# Humidity_Regulator.net
KiCad netlist of a schematic drawn in Altium Designer
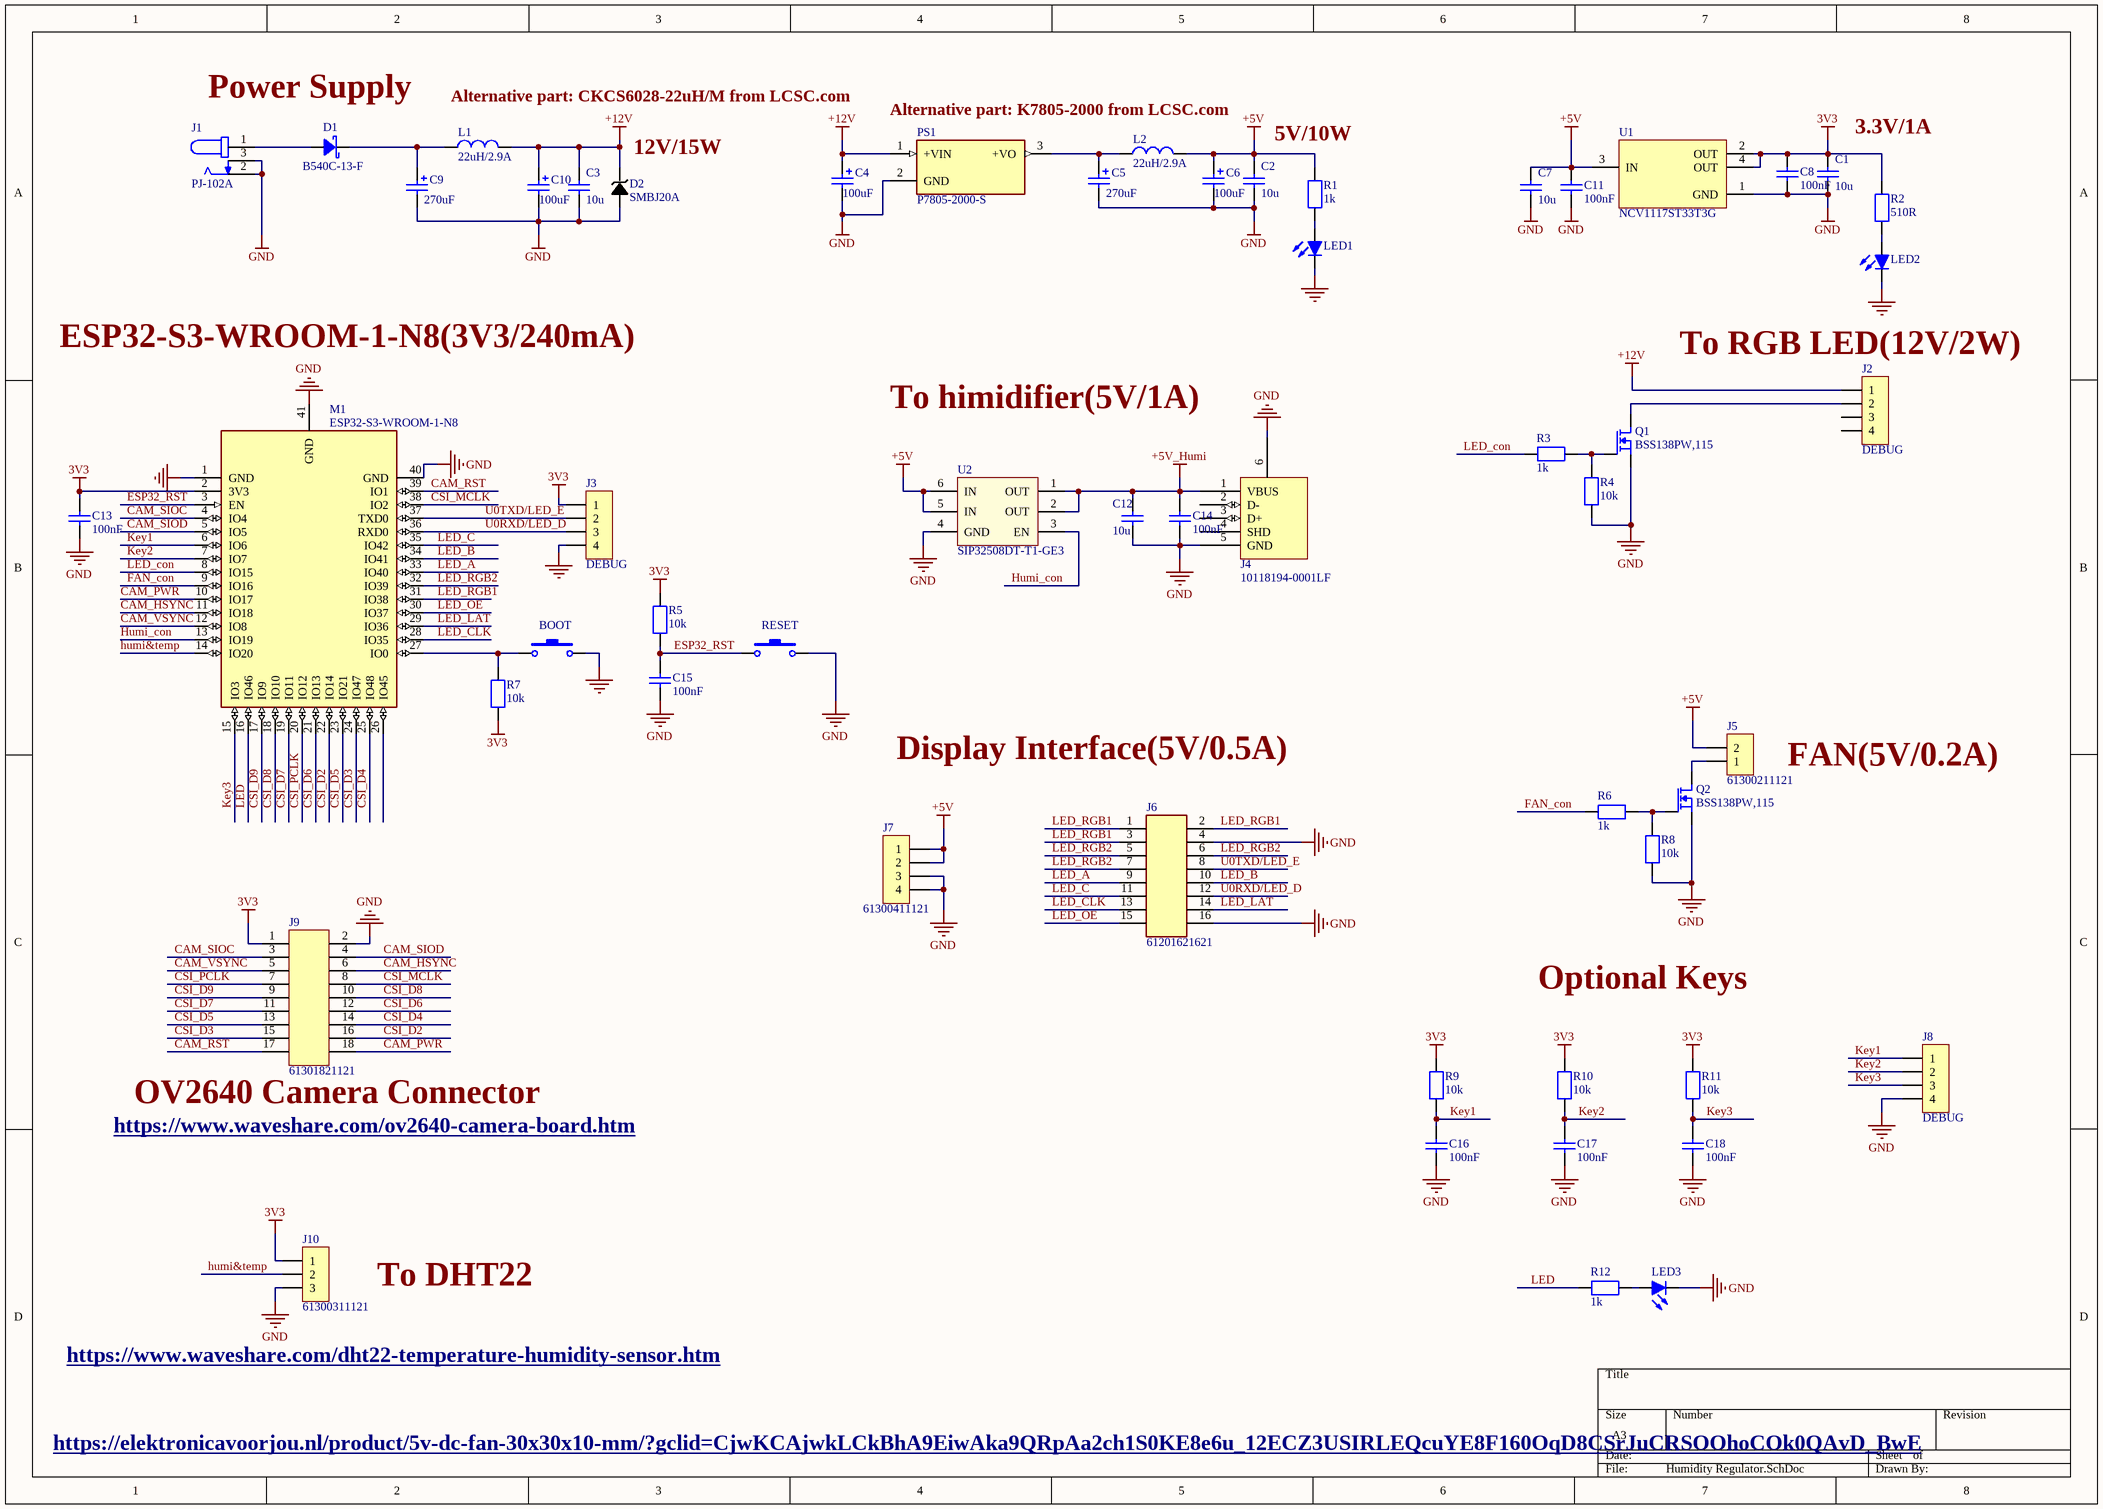
[diagram p0: Humidity Regulator.SchDoc]

(export (version "E")
  (design (tool "Eeschema 10.0.6"))
  (components
    (comp (ref "BOOT")
      (value "TL3305BF260QG")
      (footprint "SW_TL3305BF260QG")
      (description "SWITCH TACTILE SPST-NO 0.05A 12V")
      (fields (field (name "MANUFACTURER") "E-Switch"))
      (libsource (lib "Humidity Regulator") (part "TL3305BF260QG"))
    )
    (comp (ref "C1")
      (value "10u")
      (footprint "C1206")
      (description "10uF ± 10% 25V")
      (fields
        (field (name "MANUFACTURER") "Yageo")
        (field (name "MANUFACTURER PART NUMBER") "CC1206KKX7R8BB106")
      )
      (libsource (lib "Humidity Regulator") (part "10uF ± 10% 25V"))
    )
    (comp (ref "C2")
      (value "10u")
      (footprint "C1206")
      (description "10uF ± 10% 25V")
      (fields
        (field (name "MANUFACTURER") "Yageo")
        (field (name "MANUFACTURER PART NUMBER") "CC1206KKX7R8BB106")
      )
      (libsource (lib "Humidity Regulator") (part "10uF ± 10% 25V"))
    )
    (comp (ref "C3")
      (value "10u")
      (footprint "C1206")
      (description "10uF ± 10% 25V")
      (fields
        (field (name "MANUFACTURER") "Yageo")
        (field (name "MANUFACTURER PART NUMBER") "CC1206KKX7R8BB106")
      )
      (libsource (lib "Humidity Regulator") (part "10uF ± 10% 25V"))
    )
    (comp (ref "C4")
      (value "100uF")
      (footprint "CAP_EEUFC1E101S")
      (description "CAP ALUM 100UF 20% 25V SMD")
      (fields
        (field (name "MANUFACTURER PART NUMBER") "EEU-FC1E101S")
        (field (name "MANUFACTURER") "Panasonic")
      )
      (libsource (lib "Humidity Regulator") (part "EEU-FC1E101S"))
    )
    (comp (ref "C5")
      (value "270uF")
      (footprint "CAP_EEU-FK1E271B")
      (description "CAP ALUM 270UF 20% 25V SMD")
      (fields
        (field (name "MANUFACTURER PART NUMBER") "EEU-FC1E271B")
        (field (name "MANUFACTURER") "Panasonic")
      )
      (libsource (lib "Humidity Regulator") (part "EEU-FC1E271B"))
    )
    (comp (ref "C6")
      (value "100uF")
      (footprint "CAP_EEUFC1E101S")
      (description "CAP ALUM 100UF 20% 25V SMD")
      (fields
        (field (name "MANUFACTURER PART NUMBER") "EEU-FC1E101S")
        (field (name "MANUFACTURER") "Panasonic")
      )
      (libsource (lib "Humidity Regulator") (part "EEU-FC1E101S"))
    )
    (comp (ref "C7")
      (value "10u")
      (footprint "C1206")
      (description "10uF ± 10% 25V")
      (fields
        (field (name "MANUFACTURER") "Yageo")
        (field (name "MANUFACTURER PART NUMBER") "CC1206KKX7R8BB106")
      )
      (libsource (lib "Humidity Regulator") (part "10uF ± 10% 25V"))
    )
    (comp (ref "C8")
      (value "100nF")
      (footprint "C0603")
      (description "100nF ± 10% 50V")
      (fields
        (field (name "MANUFACTURER") "Yageo")
        (field (name "MANUFACTURER PART NUMBER") "CC0603KRX7R9BB104")
      )
      (libsource (lib "Humidity Regulator") (part "100nF ± 10% 50V"))
    )
    (comp (ref "C9")
      (value "270uF")
      (footprint "CAP_EEU-FK1E271B")
      (description "CAP ALUM 270UF 20% 25V SMD")
      (fields
        (field (name "MANUFACTURER PART NUMBER") "EEU-FC1E271B")
        (field (name "MANUFACTURER") "Panasonic")
      )
      (libsource (lib "Humidity Regulator") (part "EEU-FC1E271B"))
    )
    (comp (ref "C10")
      (value "100uF")
      (footprint "CAP_EEUFC1E101S")
      (description "CAP ALUM 100UF 20% 25V SMD")
      (fields
        (field (name "MANUFACTURER PART NUMBER") "EEU-FC1E101S")
        (field (name "MANUFACTURER") "Panasonic")
      )
      (libsource (lib "Humidity Regulator") (part "EEU-FC1E101S"))
    )
    (comp (ref "C11")
      (value "100nF")
      (footprint "C0603")
      (description "100nF ± 10% 50V")
      (fields
        (field (name "MANUFACTURER") "Yageo")
        (field (name "MANUFACTURER PART NUMBER") "CC0603KRX7R9BB104")
      )
      (libsource (lib "Humidity Regulator") (part "100nF ± 10% 50V"))
    )
    (comp (ref "C12")
      (value "10u")
      (footprint "C1206")
      (description "10uF ± 10% 25V")
      (fields
        (field (name "MANUFACTURER") "Yageo")
        (field (name "MANUFACTURER PART NUMBER") "CC1206KKX7R8BB106")
      )
      (libsource (lib "Humidity Regulator") (part "10uF ± 10% 25V"))
    )
    (comp (ref "C13")
      (value "100nF")
      (footprint "C0603")
      (description "100nF ± 10% 50V")
      (fields
        (field (name "MANUFACTURER") "Yageo")
        (field (name "MANUFACTURER PART NUMBER") "CC0603KRX7R9BB104")
      )
      (libsource (lib "Humidity Regulator") (part "100nF ± 10% 50V"))
    )
    (comp (ref "C14")
      (value "100nF")
      (footprint "C0603")
      (description "100nF ± 10% 50V")
      (fields
        (field (name "MANUFACTURER") "Yageo")
        (field (name "MANUFACTURER PART NUMBER") "CC0603KRX7R9BB104")
      )
      (libsource (lib "Humidity Regulator") (part "100nF ± 10% 50V"))
    )
    (comp (ref "C15")
      (value "100nF")
      (footprint "C0603")
      (description "100nF ± 10% 50V")
      (fields
        (field (name "MANUFACTURER") "Yageo")
        (field (name "MANUFACTURER PART NUMBER") "CC0603KRX7R9BB104")
      )
      (libsource (lib "Humidity Regulator") (part "100nF ± 10% 50V"))
    )
    (comp (ref "C16")
      (value "100nF")
      (footprint "C0603")
      (description "100nF ± 10% 50V")
      (fields
        (field (name "MANUFACTURER") "Yageo")
        (field (name "MANUFACTURER PART NUMBER") "CC0603KRX7R9BB104")
      )
      (libsource (lib "Humidity Regulator") (part "100nF ± 10% 50V"))
    )
    (comp (ref "C17")
      (value "100nF")
      (footprint "C0603")
      (description "100nF ± 10% 50V")
      (fields
        (field (name "MANUFACTURER") "Yageo")
        (field (name "MANUFACTURER PART NUMBER") "CC0603KRX7R9BB104")
      )
      (libsource (lib "Humidity Regulator") (part "100nF ± 10% 50V"))
    )
    (comp (ref "C18")
      (value "100nF")
      (footprint "C0603")
      (description "100nF ± 10% 50V")
      (fields
        (field (name "MANUFACTURER") "Yageo")
        (field (name "MANUFACTURER PART NUMBER") "CC0603KRX7R9BB104")
      )
      (libsource (lib "Humidity Regulator") (part "100nF ± 10% 50V"))
    )
    (comp (ref "D1")
      (value "B540C-13-F")
      (footprint "DO-214AB2")
      (description "Schottky Diodes & Rectifiers 40V 5A")
      (fields (field (name "MANUFACTURER") "Diodes"))
      (libsource (lib "Humidity Regulator") (part "B540C-13-F"))
    )
    (comp (ref "D2")
      (value "SMBJ20A")
      (footprint "DO-214AA2")
      (description "ESD Suppressors / TVS Diodes 600W, 23.4V, 5%, Unidirectional, TVS")
      (fields (field (name "MANUFACTURER") "Littelfuse"))
      (libsource (lib "Humidity Regulator") (part "ZM4746A-GS08"))
    )
    (comp (ref "J1")
      (value "PJ-102A")
      (footprint "CUI_PJ-102A")
      (description "CONN PWR JACK 2X5.5MM SOLDER")
      (fields (field (name "MANUFACTURER") "CUI Devices"))
      (libsource (lib "WirelessCharger") (part "PJ-102A"))
    )
    (comp (ref "J2")
      (value "DEBUG")
      (footprint "61300411121")
      (description "Headers & Wire Housings WR-PHD 2.54mm Hdr 4P Single Gold")
      (fields (field (name "MANUFACTURER") "Mouser") (field (name "MANUFACTURER PART NUMBER") "61300411121"))
      (libsource (lib "Humidity Regulator") (part "61300411121"))
    )
    (comp (ref "J3")
      (value "DEBUG")
      (footprint "61300411121")
      (description "Headers & Wire Housings WR-PHD 2.54mm Hdr 4P Single Gold")
      (fields (field (name "MANUFACTURER") "Mouser") (field (name "MANUFACTURER PART NUMBER") "61300411121"))
      (libsource (lib "Humidity Regulator") (part "61300411121"))
    )
    (comp (ref "J4")
      (value "10118194-0001LF")
      (footprint "10118194-0001LF")
      (description "CONN RCPT USB2.0 MICRO B SMD R/A")
      (fields (field (name "MANUFACTURER") "Amphenol FCI"))
      (libsource (lib "Humidity Regulator") (part "10118194-0001LF"))
    )
    (comp (ref "J5")
      (value "61300211121")
      (footprint "61300211121")
      (description "Headers & Wire Housings WR-PHD 2.54mm Hdr 2P Single Gold")
      (fields (field (name "MANUFACTURER") "Mouser"))
      (libsource (lib "Humidity Regulator") (part "61300211121"))
    )
    (comp (ref "J6")
      (value "61201621621")
      (footprint "61201621621:61201621621")
      (description "Connector Header Through Hole 16 position 0.100 (2.54mm)")
      (fields (field (name "MANUFACTURER") "Wurth Electronics"))
      (libsource (lib "Humidity Regulator") (part "61201621621"))
    )
    (comp (ref "J7")
      (value "61300411121")
      (footprint "61300411121")
      (description "Headers & Wire Housings WR-PHD 2.54mm Hdr 4P Single Gold")
      (fields (field (name "MANUFACTURER") "Mouser"))
      (libsource (lib "") (part "61300411121_1"))
    )
    (comp (ref "J8")
      (value "DEBUG")
      (footprint "61300411121")
      (description "Headers & Wire Housings WR-PHD 2.54mm Hdr 4P Single Gold")
      (fields (field (name "MANUFACTURER") "Mouser") (field (name "MANUFACTURER PART NUMBER") "61300411121"))
      (libsource (lib "Humidity Regulator") (part "61300411121"))
    )
    (comp (ref "J9")
      (value "61301821121")
      (footprint "61301821121")
      (description "Headers & Wire Housings WR-PHD 2.54mm Hdr 18 P Dual Str Gold")
      (fields (field (name "MANUFACTURER") "Wurth Electronics"))
      (libsource (lib "Humidity Regulator") (part "61301821121"))
    )
    (comp (ref "J10")
      (value "61300311121")
      (footprint "61300311121")
      (description "Headers & Wire Housings WR-PHD 2.54mm Hdr 3P Single Gold")
      (fields (field (name "MANUFACTURER") "Mouser"))
      (libsource (lib "Humidity Regulator") (part "61300311121"))
    )
    (comp (ref "L1")
      (value "22uH/2.9A")
      (footprint "IND_SRP6030")
      (description "Power Inductors - SMD Ind,7.1x6.6x2.8mm,22uH+/-20%,2.9A,shd")
      (fields
        (field (name "MANUFACTURER PART NUMBER") "SRP6030WA-220M")
        (field (name "MANUFACTURER") "Bourns")
      )
      (libsource (lib "Humidity Regulator") (part "SRP6030WA-220M"))
    )
    (comp (ref "L2")
      (value "22uH/2.9A")
      (footprint "IND_SRP6030")
      (description "Power Inductors - SMD Ind,7.1x6.6x2.8mm,22uH+/-20%,2.9A,shd")
      (fields
        (field (name "MANUFACTURER PART NUMBER") "SRP6030WA-220M")
        (field (name "MANUFACTURER") "Bourns")
      )
      (libsource (lib "Humidity Regulator") (part "SRP6030WA-220M"))
    )
    (comp (ref "LED1")
      (value "SML-D12U1WT86")
      (footprint "LED0603")
      (description "Typical RED GaAs LED")
      (fields (field (name "MANUFACTURER") "Rohm Semiconductor"))
      (libsource (lib "Humidity Regulator") (part "SML-D12U1WT86"))
    )
    (comp (ref "LED2")
      (value "SML-D12U1WT86")
      (footprint "LED0603")
      (description "Typical RED GaAs LED")
      (fields (field (name "MANUFACTURER") "Rohm Semiconductor"))
      (libsource (lib "Humidity Regulator") (part "SML-D12U1WT86"))
    )
    (comp (ref "LED3")
      (value "SML-D12U1WT86")
      (footprint "LED0603")
      (description "Typical RED GaAs LED")
      (fields (field (name "MANUFACTURER") "Rohm Semiconductor"))
      (libsource (lib "Humidity Regulator") (part "SML-D12U1WT86"))
    )
    (comp (ref "M1")
      (value "ESP32-S3-WROOM-1-N8")
      (footprint "ESP32-S3-WROOM-1-N8")
      (description "Bluetooth, WiFi 802.11b/g/n, Bluetooth v5.0 Transceiver Module 2.4GHz PCB Trace Surface Mount")
      (fields (field (name "MANUFACTURER") "Espressif Systems"))
      (libsource (lib "Humidity Regulator") (part "ESP32-S3-WROOM-1-N8"))
    )
    (comp (ref "PS1")
      (value "P7805-2000-S")
      (footprint "CONV_P7805-2000-S")
      (description "2 A Output Current, 6~36 Vdc Input, SIP, Non-Isolated, Dc-Dc Converter")
      (fields (field (name "MANUFACTURER") "CUI Inc."))
      (libsource (lib "P7805-2000-S") (part "P7805-2000-S"))
    )
    (comp (ref "Q1")
      (value "BSS138PW,115")
      (footprint "SOT323-3")
      (description "MOSFET, N CH, 60V, 0.2A")
      (fields (field (name "MANUFACTURER") "Nexperia"))
      (libsource (lib "Humidity Regulator") (part "BSS138PW,115"))
    )
    (comp (ref "Q2")
      (value "BSS138PW,115")
      (footprint "SOT323-3")
      (description "MOSFET, N CH, 60V, 0.2A")
      (fields (field (name "MANUFACTURER") "Nexperia"))
      (libsource (lib "Humidity Regulator") (part "BSS138PW,115"))
    )
    (comp (ref "R1")
      (value "1k")
      (footprint "R0603")
      (description "1 kOhms ±1% 0.1W")
      (fields
        (field (name "MANUFACTURER") "Yageo")
        (field (name "MANUFACTURER PART NUMBER") "RC0603FR-071KL")
      )
      (libsource (lib "Humidity Regulator") (part "1 kOhms ±1% 0.1W"))
    )
    (comp (ref "R2")
      (value "510R")
      (footprint "R0603")
      (description "510 Ohm ±1% 0.1W")
      (fields
        (field (name "MANUFACTURER") "Yageo")
        (field (name "MANUFACTURER PART NUMBER") "RC0603FR-07510RL")
      )
      (libsource (lib "Humidity Regulator") (part "510 Ohm ±1% 0.1W"))
    )
    (comp (ref "R3")
      (value "1k")
      (footprint "R0603")
      (description "1 kOhms ±1% 0.1W")
      (fields
        (field (name "MANUFACTURER") "Yageo")
        (field (name "MANUFACTURER PART NUMBER") "RC0603FR-071KL")
      )
      (libsource (lib "Humidity Regulator") (part "1 kOhms ±1% 0.1W"))
    )
    (comp (ref "R4")
      (value "10k")
      (footprint "R0603")
      (description "10 kOhms ±1% 0.1W")
      (fields
        (field (name "MANUFACTURER") "Yageo")
        (field (name "MANUFACTURER PART NUMBER") "RC0603FR-0710KL")
      )
      (libsource (lib "Humidity Regulator") (part "10 kOhms ±1% 0.1W"))
    )
    (comp (ref "R5")
      (value "10k")
      (footprint "R0603")
      (description "10 kOhms ±1% 0.1W")
      (fields
        (field (name "MANUFACTURER") "Yageo")
        (field (name "MANUFACTURER PART NUMBER") "RC0603FR-0710KL")
      )
      (libsource (lib "Humidity Regulator") (part "10 kOhms ±1% 0.1W"))
    )
    (comp (ref "R6")
      (value "1k")
      (footprint "R0603")
      (description "1 kOhms ±1% 0.1W")
      (fields
        (field (name "MANUFACTURER") "Yageo")
        (field (name "MANUFACTURER PART NUMBER") "RC0603FR-071KL")
      )
      (libsource (lib "Humidity Regulator") (part "1 kOhms ±1% 0.1W"))
    )
    (comp (ref "R7")
      (value "10k")
      (footprint "R0603")
      (description "10 kOhms ±1% 0.1W")
      (fields
        (field (name "MANUFACTURER") "Yageo")
        (field (name "MANUFACTURER PART NUMBER") "RC0603FR-0710KL")
      )
      (libsource (lib "Humidity Regulator") (part "10 kOhms ±1% 0.1W"))
    )
    (comp (ref "R8")
      (value "10k")
      (footprint "R0603")
      (description "10 kOhms ±1% 0.1W")
      (fields
        (field (name "MANUFACTURER") "Yageo")
        (field (name "MANUFACTURER PART NUMBER") "RC0603FR-0710KL")
      )
      (libsource (lib "Humidity Regulator") (part "10 kOhms ±1% 0.1W"))
    )
    (comp (ref "R9")
      (value "10k")
      (footprint "R0603")
      (description "10 kOhms ±1% 0.1W")
      (fields
        (field (name "MANUFACTURER") "Yageo")
        (field (name "MANUFACTURER PART NUMBER") "RC0603FR-0710KL")
      )
      (libsource (lib "Humidity Regulator") (part "10 kOhms ±1% 0.1W"))
    )
    (comp (ref "R10")
      (value "10k")
      (footprint "R0603")
      (description "10 kOhms ±1% 0.1W")
      (fields
        (field (name "MANUFACTURER") "Yageo")
        (field (name "MANUFACTURER PART NUMBER") "RC0603FR-0710KL")
      )
      (libsource (lib "Humidity Regulator") (part "10 kOhms ±1% 0.1W"))
    )
    (comp (ref "R11")
      (value "10k")
      (footprint "R0603")
      (description "10 kOhms ±1% 0.1W")
      (fields
        (field (name "MANUFACTURER") "Yageo")
        (field (name "MANUFACTURER PART NUMBER") "RC0603FR-0710KL")
      )
      (libsource (lib "Humidity Regulator") (part "10 kOhms ±1% 0.1W"))
    )
    (comp (ref "R12")
      (value "1k")
      (footprint "R0603")
      (description "1 kOhms ±1% 0.1W")
      (fields
        (field (name "MANUFACTURER") "Yageo")
        (field (name "MANUFACTURER PART NUMBER") "RC0603FR-071KL")
      )
      (libsource (lib "Humidity Regulator") (part "1 kOhms ±1% 0.1W"))
    )
    (comp (ref "RESET")
      (value "TL3305BF260QG")
      (footprint "SW_TL3305BF260QG")
      (description "SWITCH TACTILE SPST-NO 0.05A 12V")
      (fields (field (name "MANUFACTURER") "E-Switch"))
      (libsource (lib "Humidity Regulator") (part "TL3305BF260QG"))
    )
    (comp (ref "U1")
      (value "NCV1117ST33T3G")
      (footprint "SOT223-3")
      (description "LDO Voltage Regulators 3.3V 1.0A Automotive")
      (fields (field (name "MANUFACTURER") "onsemi"))
      (libsource (lib "Humidity Regulator") (part "NCV1117ST33T3G"))
    )
    (comp (ref "U2")
      (value "SIP32508DT-T1-GE3")
      (footprint "TSOT23-6")
      (description "Power Switch ICs - Power Distribution Slew Rate Controlled Load Switch")
      (fields (field (name "MANUFACTURER") "Vishay / Siliconix"))
      (libsource (lib "Humidity Regulator") (part "SIP32508DT-T1-GE3"))
    )
  )
  (nets
    (net (code "1") (name "+5V") (class "Default")
      (node (ref "C11") (pin "2") (pinfunction "2_2") (pintype "passive"))
      (node (ref "C2") (pin "2") (pinfunction "2_2") (pintype "passive"))
      (node (ref "C6") (pin "1") (pinfunction "1_1") (pintype "passive"))
      (node (ref "C7") (pin "2") (pinfunction "2_2") (pintype "passive"))
      (node (ref "J5") (pin "2") (pinfunction "2_2") (pintype "passive"))
      (node (ref "J7") (pin "1") (pinfunction "1_1") (pintype "passive"))
      (node (ref "J7") (pin "2") (pinfunction "2_2") (pintype "passive"))
      (node (ref "L2") (pin "2") (pinfunction "2_2") (pintype "passive"))
      (node (ref "R1") (pin "2") (pinfunction "2_2") (pintype "passive"))
      (node (ref "U1") (pin "3") (pinfunction "IN_3") (pintype "power_in"))
      (node (ref "U2") (pin "5") (pinfunction "IN_5") (pintype "passive"))
      (node (ref "U2") (pin "6") (pinfunction "IN_6") (pintype "passive"))
    )
    (net (code "2") (name "+5V_Humi") (class "Default")
      (node (ref "C12") (pin "2") (pinfunction "2_2") (pintype "passive"))
      (node (ref "C14") (pin "2") (pinfunction "2_2") (pintype "passive"))
      (node (ref "J4") (pin "1") (pinfunction "VBUS_1") (pintype "power_in"))
      (node (ref "U2") (pin "1") (pinfunction "OUT_1") (pintype "passive"))
      (node (ref "U2") (pin "2") (pinfunction "OUT_2") (pintype "passive"))
    )
    (net (code "3") (name "+12V") (class "Default")
      (node (ref "C10") (pin "1") (pinfunction "1_1") (pintype "passive"))
      (node (ref "C3") (pin "2") (pinfunction "2_2") (pintype "passive"))
      (node (ref "C4") (pin "1") (pinfunction "1_1") (pintype "passive"))
      (node (ref "D2") (pin "C") (pinfunction "C_C") (pintype "passive"))
      (node (ref "J2") (pin "1") (pinfunction "1_1") (pintype "passive"))
      (node (ref "L1") (pin "2") (pinfunction "2_2") (pintype "passive"))
      (node (ref "PS1") (pin "1") (pinfunction "+VIN_1") (pintype "input"))
    )
    (net (code "4") (name "/CAM_HSYNC") (class "Default")
      (node (ref "J9") (pin "6") (pinfunction "6_6") (pintype "passive"))
      (node (ref "M1") (pin "11") (pinfunction "IO18_11") (pintype "bidirectional"))
    )
    (net (code "5") (name "/CAM_PWR") (class "Default")
      (node (ref "J9") (pin "18") (pinfunction "18_18") (pintype "passive"))
      (node (ref "M1") (pin "10") (pinfunction "IO17_10") (pintype "bidirectional"))
    )
    (net (code "6") (name "/CAM_RST") (class "Default")
      (node (ref "J9") (pin "17") (pinfunction "17_17") (pintype "passive"))
      (node (ref "M1") (pin "39") (pinfunction "IO1_39") (pintype "bidirectional"))
    )
    (net (code "7") (name "/CAM_SIOC") (class "Default")
      (node (ref "J9") (pin "3") (pinfunction "3_3") (pintype "passive"))
      (node (ref "M1") (pin "4") (pinfunction "IO4_4") (pintype "bidirectional"))
    )
    (net (code "8") (name "/CAM_SIOD") (class "Default")
      (node (ref "J9") (pin "4") (pinfunction "4_4") (pintype "passive"))
      (node (ref "M1") (pin "5") (pinfunction "IO5_5") (pintype "bidirectional"))
    )
    (net (code "9") (name "/CAM_VSYNC") (class "Default")
      (node (ref "J9") (pin "5") (pinfunction "5_5") (pintype "passive"))
      (node (ref "M1") (pin "12") (pinfunction "IO8_12") (pintype "bidirectional"))
    )
    (net (code "10") (name "/CSI_D2") (class "Default")
      (node (ref "J9") (pin "16") (pinfunction "16_16") (pintype "passive"))
      (node (ref "M1") (pin "22") (pinfunction "IO14_22") (pintype "bidirectional"))
    )
    (net (code "11") (name "/CSI_D3") (class "Default")
      (node (ref "J9") (pin "15") (pinfunction "15_15") (pintype "passive"))
      (node (ref "M1") (pin "24") (pinfunction "IO47_24") (pintype "bidirectional"))
    )
    (net (code "12") (name "/CSI_D4") (class "Default")
      (node (ref "J9") (pin "14") (pinfunction "14_14") (pintype "passive"))
      (node (ref "M1") (pin "25") (pinfunction "IO48_25") (pintype "bidirectional"))
    )
    (net (code "13") (name "/CSI_D5") (class "Default")
      (node (ref "J9") (pin "13") (pinfunction "13_13") (pintype "passive"))
      (node (ref "M1") (pin "23") (pinfunction "IO21_23") (pintype "bidirectional"))
    )
    (net (code "14") (name "/CSI_D6") (class "Default")
      (node (ref "J9") (pin "12") (pinfunction "12_12") (pintype "passive"))
      (node (ref "M1") (pin "21") (pinfunction "IO13_21") (pintype "bidirectional"))
    )
    (net (code "15") (name "/CSI_D7") (class "Default")
      (node (ref "J9") (pin "11") (pinfunction "11_11") (pintype "passive"))
      (node (ref "M1") (pin "19") (pinfunction "IO11_19") (pintype "bidirectional"))
    )
    (net (code "16") (name "/CSI_D8") (class "Default")
      (node (ref "J9") (pin "10") (pinfunction "10_10") (pintype "passive"))
      (node (ref "M1") (pin "18") (pinfunction "IO10_18") (pintype "bidirectional"))
    )
    (net (code "17") (name "/CSI_D9") (class "Default")
      (node (ref "J9") (pin "9") (pinfunction "9_9") (pintype "passive"))
      (node (ref "M1") (pin "17") (pinfunction "IO9_17") (pintype "bidirectional"))
    )
    (net (code "18") (name "/CSI_MCLK") (class "Default")
      (node (ref "J9") (pin "8") (pinfunction "8_8") (pintype "passive"))
      (node (ref "M1") (pin "38") (pinfunction "IO2_38") (pintype "bidirectional"))
    )
    (net (code "19") (name "/CSI_PCLK") (class "Default")
      (node (ref "J9") (pin "7") (pinfunction "7_7") (pintype "passive"))
      (node (ref "M1") (pin "20") (pinfunction "IO12_20") (pintype "bidirectional"))
    )
    (net (code "20") (name "/ESP32_RST") (class "Default")
      (node (ref "C15") (pin "2") (pinfunction "2_2") (pintype "passive"))
      (node (ref "M1") (pin "3") (pinfunction "EN_3") (pintype "input"))
      (node (ref "R5") (pin "1") (pinfunction "1_1") (pintype "passive"))
      (node (ref "RESET") (pin "1") (pinfunction "1_1") (pintype "passive"))
    )
    (net (code "21") (name "/FAN_con") (class "Default")
      (node (ref "M1") (pin "9") (pinfunction "IO16_9") (pintype "bidirectional"))
      (node (ref "R6") (pin "1") (pinfunction "1_1") (pintype "passive"))
    )
    (net (code "22") (name "/Humi_con") (class "Default")
      (node (ref "M1") (pin "13") (pinfunction "IO19_13") (pintype "bidirectional"))
      (node (ref "U2") (pin "3") (pinfunction "EN_3") (pintype "passive"))
    )
    (net (code "23") (name "/Key1") (class "Default")
      (node (ref "C16") (pin "2") (pinfunction "2_2") (pintype "passive"))
      (node (ref "J8") (pin "1") (pinfunction "1_1") (pintype "passive"))
      (node (ref "M1") (pin "6") (pinfunction "IO6_6") (pintype "bidirectional"))
      (node (ref "R9") (pin "1") (pinfunction "1_1") (pintype "passive"))
    )
    (net (code "24") (name "/Key2") (class "Default")
      (node (ref "C17") (pin "2") (pinfunction "2_2") (pintype "passive"))
      (node (ref "J8") (pin "2") (pinfunction "2_2") (pintype "passive"))
      (node (ref "M1") (pin "7") (pinfunction "IO7_7") (pintype "bidirectional"))
      (node (ref "R10") (pin "1") (pinfunction "1_1") (pintype "passive"))
    )
    (net (code "25") (name "/Key3") (class "Default")
      (node (ref "C18") (pin "2") (pinfunction "2_2") (pintype "passive"))
      (node (ref "J8") (pin "3") (pinfunction "3_3") (pintype "passive"))
      (node (ref "M1") (pin "15") (pinfunction "IO3_15") (pintype "bidirectional"))
      (node (ref "R11") (pin "1") (pinfunction "1_1") (pintype "passive"))
    )
    (net (code "26") (name "/LED") (class "Default")
      (node (ref "M1") (pin "16") (pinfunction "IO46_16") (pintype "bidirectional"))
      (node (ref "R12") (pin "2") (pinfunction "2_2") (pintype "passive"))
    )
    (net (code "27") (name "/LED_A") (class "Default")
      (node (ref "J6") (pin "9") (pinfunction "9_9") (pintype "passive"))
      (node (ref "M1") (pin "33") (pinfunction "IO40_33") (pintype "bidirectional"))
    )
    (net (code "28") (name "/LED_B") (class "Default")
      (node (ref "J6") (pin "10") (pinfunction "10_10") (pintype "passive"))
      (node (ref "M1") (pin "34") (pinfunction "IO41_34") (pintype "bidirectional"))
    )
    (net (code "29") (name "/LED_C") (class "Default")
      (node (ref "J6") (pin "11") (pinfunction "11_11") (pintype "passive"))
      (node (ref "M1") (pin "35") (pinfunction "IO42_35") (pintype "bidirectional"))
    )
    (net (code "30") (name "/LED_CLK") (class "Default")
      (node (ref "J6") (pin "13") (pinfunction "13_13") (pintype "passive"))
      (node (ref "M1") (pin "28") (pinfunction "IO35_28") (pintype "bidirectional"))
    )
    (net (code "31") (name "/LED_LAT") (class "Default")
      (node (ref "J6") (pin "14") (pinfunction "14_14") (pintype "passive"))
      (node (ref "M1") (pin "29") (pinfunction "IO36_29") (pintype "bidirectional"))
    )
    (net (code "32") (name "/LED_OE") (class "Default")
      (node (ref "J6") (pin "15") (pinfunction "15_15") (pintype "passive"))
      (node (ref "M1") (pin "30") (pinfunction "IO37_30") (pintype "bidirectional"))
    )
    (net (code "33") (name "/LED_RGB1") (class "Default")
      (node (ref "J6") (pin "1") (pinfunction "1_1") (pintype "passive"))
      (node (ref "J6") (pin "2") (pinfunction "2_2") (pintype "passive"))
      (node (ref "J6") (pin "3") (pinfunction "3_3") (pintype "passive"))
      (node (ref "M1") (pin "31") (pinfunction "IO38_31") (pintype "bidirectional"))
    )
    (net (code "34") (name "/LED_RGB2") (class "Default")
      (node (ref "J6") (pin "5") (pinfunction "5_5") (pintype "passive"))
      (node (ref "J6") (pin "6") (pinfunction "6_6") (pintype "passive"))
      (node (ref "J6") (pin "7") (pinfunction "7_7") (pintype "passive"))
      (node (ref "M1") (pin "32") (pinfunction "IO39_32") (pintype "bidirectional"))
    )
    (net (code "35") (name "/LED_con") (class "Default")
      (node (ref "M1") (pin "8") (pinfunction "IO15_8") (pintype "bidirectional"))
      (node (ref "R3") (pin "1") (pinfunction "1_1") (pintype "passive"))
    )
    (net (code "36") (name "/U0RXD{slash}LED_D") (class "Default")
      (node (ref "J3") (pin "3") (pinfunction "3_3") (pintype "passive"))
      (node (ref "J6") (pin "12") (pinfunction "12_12") (pintype "passive"))
      (node (ref "M1") (pin "36") (pinfunction "RXD0_36") (pintype "bidirectional"))
    )
    (net (code "37") (name "/U0TXD{slash}LED_E") (class "Default")
      (node (ref "J3") (pin "2") (pinfunction "2_2") (pintype "passive"))
      (node (ref "J6") (pin "8") (pinfunction "8_8") (pintype "passive"))
      (node (ref "M1") (pin "37") (pinfunction "TXD0_37") (pintype "bidirectional"))
    )
    (net (code "38") (name "/humi&temp") (class "Default")
      (node (ref "J10") (pin "2") (pinfunction "2_2") (pintype "passive"))
      (node (ref "M1") (pin "14") (pinfunction "IO20_14") (pintype "bidirectional"))
    )
    (net (code "39") (name "3V3") (class "Default")
      (node (ref "C1") (pin "2") (pinfunction "2_2") (pintype "passive"))
      (node (ref "C13") (pin "2") (pinfunction "2_2") (pintype "passive"))
      (node (ref "C8") (pin "2") (pinfunction "2_2") (pintype "passive"))
      (node (ref "J10") (pin "1") (pinfunction "1_1") (pintype "passive"))
      (node (ref "J3") (pin "1") (pinfunction "1_1") (pintype "passive"))
      (node (ref "J9") (pin "1") (pinfunction "1_1") (pintype "passive"))
      (node (ref "M1") (pin "2") (pinfunction "3V3_2") (pintype "power_in"))
      (node (ref "R10") (pin "2") (pinfunction "2_2") (pintype "passive"))
      (node (ref "R11") (pin "2") (pinfunction "2_2") (pintype "passive"))
      (node (ref "R2") (pin "2") (pinfunction "2_2") (pintype "passive"))
      (node (ref "R5") (pin "2") (pinfunction "2_2") (pintype "passive"))
      (node (ref "R7") (pin "2") (pinfunction "2_2") (pintype "passive"))
      (node (ref "R9") (pin "2") (pinfunction "2_2") (pintype "passive"))
      (node (ref "U1") (pin "2") (pinfunction "OUT_2") (pintype "power_in"))
      (node (ref "U1") (pin "4") (pinfunction "OUT_4") (pintype "power_in"))
    )
    (net (code "40") (name "GND") (class "Default")
      (node (ref "BOOT") (pin "2") (pinfunction "2_2") (pintype "passive"))
      (node (ref "C1") (pin "1") (pinfunction "1_1") (pintype "passive"))
      (node (ref "C10") (pin "2") (pinfunction "2_2") (pintype "passive"))
      (node (ref "C11") (pin "1") (pinfunction "1_1") (pintype "passive"))
      (node (ref "C12") (pin "1") (pinfunction "1_1") (pintype "passive"))
      (node (ref "C13") (pin "1") (pinfunction "1_1") (pintype "passive"))
      (node (ref "C14") (pin "1") (pinfunction "1_1") (pintype "passive"))
      (node (ref "C15") (pin "1") (pinfunction "1_1") (pintype "passive"))
      (node (ref "C16") (pin "1") (pinfunction "1_1") (pintype "passive"))
      (node (ref "C17") (pin "1") (pinfunction "1_1") (pintype "passive"))
      (node (ref "C18") (pin "1") (pinfunction "1_1") (pintype "passive"))
      (node (ref "C2") (pin "1") (pinfunction "1_1") (pintype "passive"))
      (node (ref "C3") (pin "1") (pinfunction "1_1") (pintype "passive"))
      (node (ref "C4") (pin "2") (pinfunction "2_2") (pintype "passive"))
      (node (ref "C5") (pin "2") (pinfunction "2_2") (pintype "passive"))
      (node (ref "C6") (pin "2") (pinfunction "2_2") (pintype "passive"))
      (node (ref "C7") (pin "1") (pinfunction "1_1") (pintype "passive"))
      (node (ref "C8") (pin "1") (pinfunction "1_1") (pintype "passive"))
      (node (ref "C9") (pin "2") (pinfunction "2_2") (pintype "passive"))
      (node (ref "D2") (pin "A") (pinfunction "A_A") (pintype "passive"))
      (node (ref "J1") (pin "2") (pinfunction "2_2") (pintype "passive"))
      (node (ref "J1") (pin "3") (pinfunction "3_3") (pintype "passive"))
      (node (ref "J10") (pin "3") (pinfunction "3_3") (pintype "passive"))
      (node (ref "J3") (pin "4") (pinfunction "4_4") (pintype "passive"))
      (node (ref "J4") (pin "5") (pinfunction "GND_5") (pintype "power_in"))
      (node (ref "J4") (pin "6") (pintype "passive"))
      (node (ref "J6") (pin "16") (pinfunction "16_16") (pintype "passive"))
      (node (ref "J6") (pin "4") (pinfunction "4_4") (pintype "passive"))
      (node (ref "J7") (pin "3") (pinfunction "3_3") (pintype "passive"))
      (node (ref "J7") (pin "4") (pinfunction "4_4") (pintype "passive"))
      (node (ref "J8") (pin "4") (pinfunction "4_4") (pintype "passive"))
      (node (ref "J9") (pin "2") (pinfunction "2_2") (pintype "passive"))
      (node (ref "LED1") (pin "C") (pinfunction "C_C") (pintype "passive"))
      (node (ref "LED2") (pin "C") (pinfunction "C_C") (pintype "passive"))
      (node (ref "LED3") (pin "C") (pinfunction "C_C") (pintype "passive"))
      (node (ref "M1") (pin "1") (pinfunction "GND_1") (pintype "power_in"))
      (node (ref "M1") (pin "40") (pinfunction "GND_40") (pintype "power_in"))
      (node (ref "M1") (pin "41") (pinfunction "GND_41") (pintype "power_in"))
      (node (ref "PS1") (pin "2") (pinfunction "GND_2") (pintype "power_in"))
      (node (ref "Q1") (pin "2") (pinfunction "S_2") (pintype "passive"))
      (node (ref "Q2") (pin "2") (pinfunction "S_2") (pintype "passive"))
      (node (ref "R4") (pin "1") (pinfunction "1_1") (pintype "passive"))
      (node (ref "R8") (pin "1") (pinfunction "1_1") (pintype "passive"))
      (node (ref "RESET") (pin "2") (pinfunction "2_2") (pintype "passive"))
      (node (ref "U1") (pin "1") (pinfunction "GND_1") (pintype "power_in"))
      (node (ref "U2") (pin "4") (pinfunction "GND_4") (pintype "passive"))
    )
    (net (code "41") (name "Net-(C9-Pad1)") (class "Default")
      (node (ref "C9") (pin "1") (pinfunction "1_1") (pintype "passive"))
      (node (ref "D1") (pin "C") (pinfunction "C_C") (pintype "passive"))
      (node (ref "L1") (pin "1") (pinfunction "1_1") (pintype "passive"))
    )
    (net (code "42") (name "Net-(D1-PadA)") (class "Default")
      (node (ref "D1") (pin "A") (pinfunction "A_A") (pintype "passive"))
      (node (ref "J1") (pin "1") (pinfunction "1_1") (pintype "passive"))
    )
    (net (code "43") (name "Net-(LED1-PadA)") (class "Default")
      (node (ref "LED1") (pin "A") (pinfunction "A_A") (pintype "passive"))
      (node (ref "R1") (pin "1") (pinfunction "1_1") (pintype "passive"))
    )
    (net (code "44") (name "Net-(LED2-PadA)") (class "Default")
      (node (ref "LED2") (pin "A") (pinfunction "A_A") (pintype "passive"))
      (node (ref "R2") (pin "1") (pinfunction "1_1") (pintype "passive"))
    )
    (net (code "45") (name "Net-(LED3-PadA)") (class "Default")
      (node (ref "LED3") (pin "A") (pinfunction "A_A") (pintype "passive"))
      (node (ref "R12") (pin "1") (pinfunction "1_1") (pintype "passive"))
    )
    (net (code "46") (name "Net-(M1-IO0)") (class "Default")
      (node (ref "BOOT") (pin "1") (pinfunction "1_1") (pintype "passive"))
      (node (ref "M1") (pin "27") (pinfunction "IO0_27") (pintype "bidirectional"))
      (node (ref "R7") (pin "1") (pinfunction "1_1") (pintype "passive"))
    )
    (net (code "47") (name "Net-(PS1-+VO)") (class "Default")
      (node (ref "C5") (pin "1") (pinfunction "1_1") (pintype "passive"))
      (node (ref "L2") (pin "1") (pinfunction "1_1") (pintype "passive"))
      (node (ref "PS1") (pin "3") (pinfunction "+VO_3") (pintype "output"))
    )
    (net (code "48") (name "Net-(Q1-D)") (class "Default")
      (node (ref "J2") (pin "2") (pinfunction "2_2") (pintype "passive"))
      (node (ref "Q1") (pin "3") (pinfunction "D_3") (pintype "passive"))
    )
    (net (code "49") (name "Net-(Q1-G)") (class "Default")
      (node (ref "Q1") (pin "1") (pinfunction "G_1") (pintype "passive"))
      (node (ref "R3") (pin "2") (pinfunction "2_2") (pintype "passive"))
      (node (ref "R4") (pin "2") (pinfunction "2_2") (pintype "passive"))
    )
    (net (code "50") (name "Net-(Q2-D)") (class "Default")
      (node (ref "J5") (pin "1") (pinfunction "1_1") (pintype "passive"))
      (node (ref "Q2") (pin "3") (pinfunction "D_3") (pintype "passive"))
    )
    (net (code "51") (name "Net-(Q2-G)") (class "Default")
      (node (ref "Q2") (pin "1") (pinfunction "G_1") (pintype "passive"))
      (node (ref "R6") (pin "2") (pinfunction "2_2") (pintype "passive"))
      (node (ref "R8") (pin "2") (pinfunction "2_2") (pintype "passive"))
    )
    (net (code "52") (name "unconnected-(J2-Pad3)") (class "Default")
      (node (ref "J2") (pin "3") (pinfunction "3_3") (pintype "passive"))
    )
    (net (code "53") (name "unconnected-(J2-Pad4)") (class "Default")
      (node (ref "J2") (pin "4") (pinfunction "4_4") (pintype "passive"))
    )
    (net (code "54") (name "unconnected-(J4-D+-Pad3)") (class "Default")
      (node (ref "J4") (pin "3") (pinfunction "D+_3") (pintype "bidirectional"))
    )
    (net (code "55") (name "unconnected-(J4-D--Pad2)") (class "Default")
      (node (ref "J4") (pin "2") (pinfunction "D-_2") (pintype "bidirectional"))
    )
    (net (code "56") (name "unconnected-(J4-SHD-Pad4)") (class "Default")
      (node (ref "J4") (pin "4") (pinfunction "SHD_4") (pintype "passive"))
    )
    (net (code "57") (name "unconnected-(M1-IO45-Pad26)") (class "Default")
      (node (ref "M1") (pin "26") (pinfunction "IO45_26") (pintype "bidirectional"))
    )
  )
)
